# McPiFace-Pi4-Aerial-V2.net
KiCad netlist of a schematic drawn in EAGLE
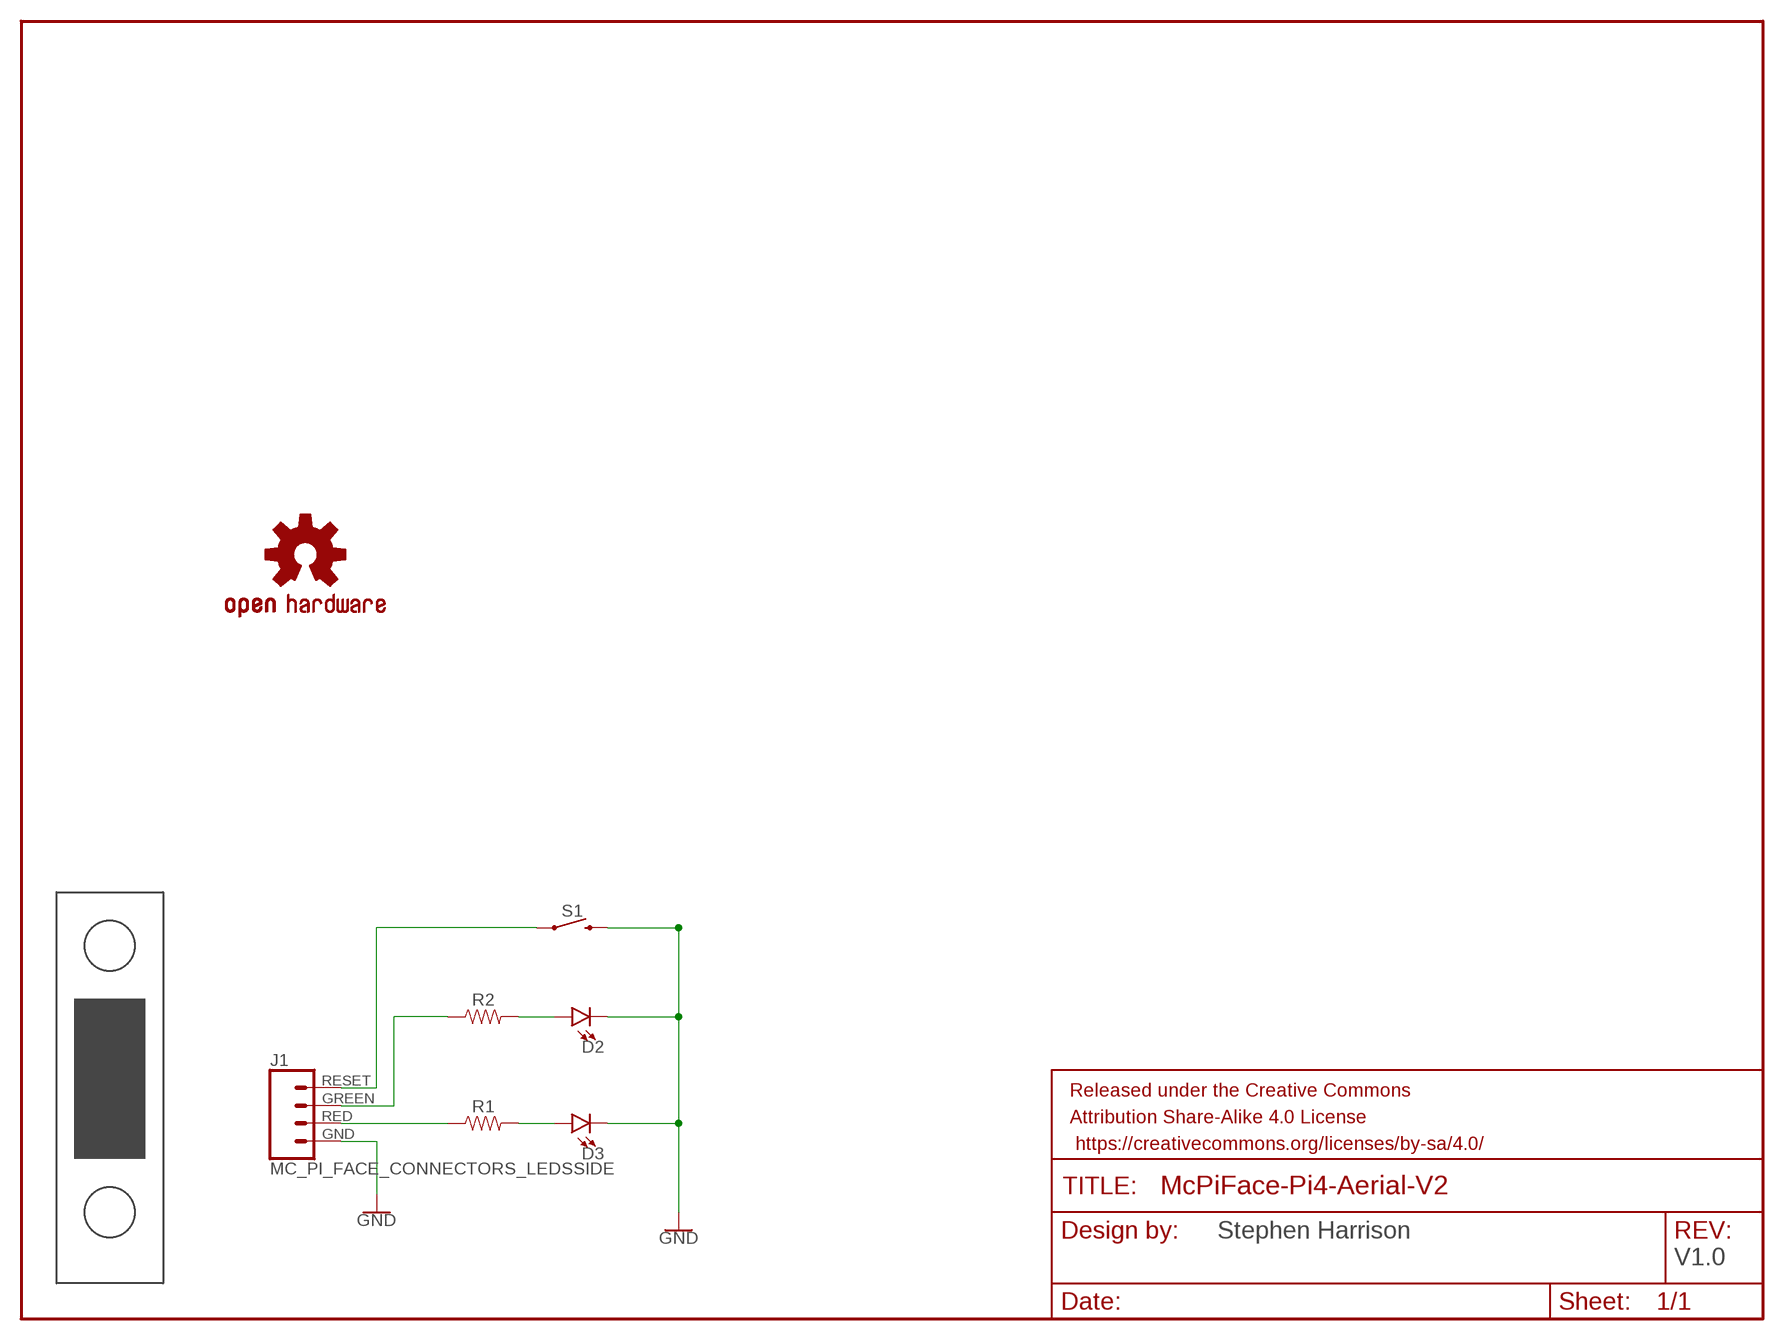
[diagram p0: schematic, sheet 1]

(export (version "E")
  (design (tool "Eeschema 10.0.6"))
  (components
    (comp (ref "D2")
      (value "LEDLED-1206-BOTTOM-2.0MM-GREEN")
      (footprint "eagle-import:LED-1206-BOTTOM-2.0MM")
      (libsource (lib "eagle-import") (part "LEDLED-1206-BOTTOM-2.0MM-GREEN"))
    )
    (comp (ref "D3")
      (value "LEDLED-1206-BOTTOM-2.0MM-RED")
      (footprint "eagle-import:LED-1206-BOTTOM-2.0MM")
      (libsource (lib "eagle-import") (part "LEDLED-1206-BOTTOM-2.0MM-RED"))
    )
    (comp (ref "FRAME1")
      (value "FRAME-LETTER")
      (footprint "eagle-import:CREATIVE_COMMONS")
      (libsource (lib "eagle-import") (part "FRAME-LETTER"))
    )
    (comp (ref "J1")
      (value "MC_PI_FACE_CONNECTORS_LEDSSIDE")
      (footprint "eagle-import:JST-4-SH-1.0MM-SIDE")
      (fields (field (name "MFG") "SM04B-SRSS-TB(LF)(SN)"))
      (libsource (lib "eagle-import") (part "MC_PI_FACE_CONNECTORS_LEDSSIDE"))
    )
    (comp (ref "LOGO1")
      (value "OSHW-LOGOL")
      (footprint "eagle-import:OSHW-LOGO-L")
      (libsource (lib "eagle-import") (part "OSHW-LOGOL"))
    )
    (comp (ref "R1")
      (value "RESISTOR0805")
      (footprint "eagle-import:0805")
      (libsource (lib "eagle-import") (part "RESISTOR0805"))
    )
    (comp (ref "R2")
      (value "RESISTOR0805")
      (footprint "eagle-import:0805")
      (libsource (lib "eagle-import") (part "RESISTOR0805"))
    )
    (comp (ref "S1")
      (value "MOMENTARY-SWITCH-SPSTTACKTILE_SWITCH_PTH_6.0MM_NO_TOP_RESIST")
      (footprint "eagle-import:TACTILE_SWITCH_PTH_6.0MM_NO_TOP_RESIST")
      (libsource (lib "eagle-import") (part "MOMENTARY-SWITCH-SPSTTACKTILE_SWITCH_PTH_6.0MM_NO_TOP_RESIST"))
    )
    (comp (ref "U$1")
      (value "MC_PI_4_FACE_PANELDOUBLE")
      (footprint "eagle-import:MC_PI_4-DOUBLE_FACE")
      (libsource (lib "eagle-import") (part "MC_PI_4_FACE_PANELDOUBLE"))
    )
  )
  (nets
    (net (code "1") (name "GND") (class "Default")
      (node (ref "D2") (pin "C") (pinfunction "C_C") (pintype "passive"))
      (node (ref "D3") (pin "C") (pinfunction "C_C") (pintype "passive"))
      (node (ref "J1") (pin "GND") (pinfunction "GND_GND") (pintype "power_in"))
      (node (ref "S1") (pin "3") (pinfunction "2_3") (pintype "passive"))
    )
    (net (code "2") (name "Net-(D2-PadA)") (class "Default")
      (node (ref "D2") (pin "A") (pinfunction "A_A") (pintype "passive"))
      (node (ref "R2") (pin "2") (pinfunction "2_2") (pintype "passive"))
    )
    (net (code "3") (name "Net-(D3-PadA)") (class "Default")
      (node (ref "D3") (pin "A") (pinfunction "A_A") (pintype "passive"))
      (node (ref "R1") (pin "2") (pinfunction "2_2") (pintype "passive"))
    )
    (net (code "4") (name "Net-(J1-PadGREEN)") (class "Default")
      (node (ref "J1") (pin "GREEN") (pinfunction "GREEN_GREEN") (pintype "passive"))
      (node (ref "R2") (pin "1") (pinfunction "1_1") (pintype "passive"))
    )
    (net (code "5") (name "Net-(J1-PadRED)") (class "Default")
      (node (ref "J1") (pin "RED") (pinfunction "RED_RED") (pintype "passive"))
      (node (ref "R1") (pin "1") (pinfunction "1_1") (pintype "passive"))
    )
    (net (code "6") (name "Net-(J1-PadRESET)") (class "Default")
      (node (ref "J1") (pin "RESET") (pinfunction "RESET_RESET") (pintype "passive"))
      (node (ref "S1") (pin "1") (pinfunction "1_1") (pintype "passive"))
    )
  )
)
